# Controller_Board_Interface.net
KiCad netlist of a schematic drawn in Altium Designer
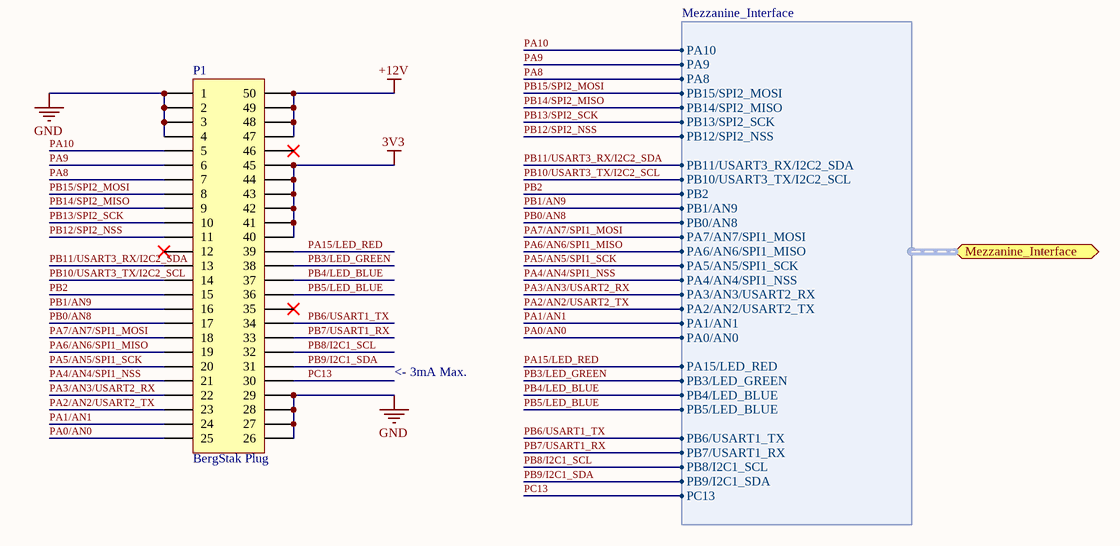
[diagram p0: Controller_Board_Interface.SchDoc]

(export (version "E")
  (design (tool "Eeschema 10.0.6"))
  (components
    (comp (ref "P1")
      (value "CONN 50POS Bergstak Plug 0.02\"")
      (footprint "CONN, Bergstak 50 Pos Plug")
      (description "50 Position Connector Plug, Outer Shroud Contacts Surface Mount Gold")
      (fields (field (name "SERIES") "BergStak Plug"))
      (libsource (lib "Schematic Diagrams") (part "CONN 50POS Bergstak Plug 0.02{dblquote}"))
    )
  )
  (nets
    (net (code "2") (name "+12V") (class "Default")
      (node (ref "P1") (pin "47") (pinfunction "47_47") (pintype "passive"))
      (node (ref "P1") (pin "48") (pinfunction "48_48") (pintype "passive"))
      (node (ref "P1") (pin "49") (pinfunction "49_49") (pintype "passive"))
      (node (ref "P1") (pin "50") (pinfunction "50_50") (pintype "passive"))
    )
    (net (code "3") (name "/PA0{slash}AN0") (class "Default")
      (node (ref "P1") (pin "25") (pinfunction "25_25") (pintype "passive"))
    )
    (net (code "4") (name "/PA1{slash}AN1") (class "Default")
      (node (ref "P1") (pin "24") (pinfunction "24_24") (pintype "passive"))
    )
    (net (code "5") (name "/PA2{slash}AN2{slash}USART2_TX") (class "Default")
      (node (ref "P1") (pin "23") (pinfunction "23_23") (pintype "passive"))
    )
    (net (code "6") (name "/PA3{slash}AN3{slash}USART2_RX") (class "Default")
      (node (ref "P1") (pin "22") (pinfunction "22_22") (pintype "passive"))
    )
    (net (code "7") (name "/PA4{slash}AN4{slash}SPI1_NSS") (class "Default")
      (node (ref "P1") (pin "21") (pinfunction "21_21") (pintype "passive"))
    )
    (net (code "8") (name "/PA5{slash}AN5{slash}SPI1_SCK") (class "Default")
      (node (ref "P1") (pin "20") (pinfunction "20_20") (pintype "passive"))
    )
    (net (code "9") (name "/PA6{slash}AN6{slash}SPI1_MISO") (class "Default")
      (node (ref "P1") (pin "19") (pinfunction "19_19") (pintype "passive"))
    )
    (net (code "10") (name "/PA7{slash}AN7{slash}SPI1_MOSI") (class "Default")
      (node (ref "P1") (pin "18") (pinfunction "18_18") (pintype "passive"))
    )
    (net (code "11") (name "/PA8") (class "Default")
      (node (ref "P1") (pin "7") (pinfunction "7_7") (pintype "passive"))
    )
    (net (code "12") (name "/PA9") (class "Default")
      (node (ref "P1") (pin "6") (pinfunction "6_6") (pintype "passive"))
    )
    (net (code "13") (name "/PA10") (class "Default")
      (node (ref "P1") (pin "5") (pinfunction "5_5") (pintype "passive"))
    )
    (net (code "14") (name "/PA15{slash}LED_RED") (class "Default")
      (node (ref "P1") (pin "39") (pinfunction "39_39") (pintype "passive"))
    )
    (net (code "15") (name "/PB0{slash}AN8") (class "Default")
      (node (ref "P1") (pin "17") (pinfunction "17_17") (pintype "passive"))
    )
    (net (code "16") (name "/PB1{slash}AN9") (class "Default")
      (node (ref "P1") (pin "16") (pinfunction "16_16") (pintype "passive"))
    )
    (net (code "17") (name "/PB2") (class "Default")
      (node (ref "P1") (pin "15") (pinfunction "15_15") (pintype "passive"))
    )
    (net (code "18") (name "/PB3{slash}LED_GREEN") (class "Default")
      (node (ref "P1") (pin "38") (pinfunction "38_38") (pintype "passive"))
    )
    (net (code "19") (name "/PB4{slash}LED_BLUE") (class "Default")
      (node (ref "P1") (pin "37") (pinfunction "37_37") (pintype "passive"))
    )
    (net (code "20") (name "/PB5{slash}LED_BLUE") (class "Default")
      (node (ref "P1") (pin "36") (pinfunction "36_36") (pintype "passive"))
    )
    (net (code "21") (name "/PB6{slash}USART1_TX") (class "Default")
      (node (ref "P1") (pin "34") (pinfunction "34_34") (pintype "passive"))
    )
    (net (code "22") (name "/PB7{slash}USART1_RX") (class "Default")
      (node (ref "P1") (pin "33") (pinfunction "33_33") (pintype "passive"))
    )
    (net (code "23") (name "/PB8{slash}I2C1_SCL") (class "Default")
      (node (ref "P1") (pin "32") (pinfunction "32_32") (pintype "passive"))
    )
    (net (code "24") (name "/PB9{slash}I2C1_SDA") (class "Default")
      (node (ref "P1") (pin "31") (pinfunction "31_31") (pintype "passive"))
    )
    (net (code "25") (name "/PB10{slash}USART3_TX{slash}I2C2_SCL") (class "Default")
      (node (ref "P1") (pin "14") (pinfunction "14_14") (pintype "passive"))
    )
    (net (code "26") (name "/PB11{slash}USART3_RX{slash}I2C2_SDA") (class "Default")
      (node (ref "P1") (pin "13") (pinfunction "13_13") (pintype "passive"))
    )
    (net (code "27") (name "/PB12{slash}SPI2_NSS") (class "Default")
      (node (ref "P1") (pin "11") (pinfunction "11_11") (pintype "passive"))
    )
    (net (code "28") (name "/PB13{slash}SPI2_SCK") (class "Default")
      (node (ref "P1") (pin "10") (pinfunction "10_10") (pintype "passive"))
    )
    (net (code "29") (name "/PB14{slash}SPI2_MISO") (class "Default")
      (node (ref "P1") (pin "9") (pinfunction "9_9") (pintype "passive"))
    )
    (net (code "30") (name "/PB15{slash}SPI2_MOSI") (class "Default")
      (node (ref "P1") (pin "8") (pinfunction "8_8") (pintype "passive"))
    )
    (net (code "31") (name "/PC13") (class "Default")
      (node (ref "P1") (pin "30") (pinfunction "30_30") (pintype "passive"))
    )
    (net (code "33") (name "3V3") (class "Default")
      (node (ref "P1") (pin "40") (pinfunction "40_40") (pintype "passive"))
      (node (ref "P1") (pin "41") (pinfunction "41_41") (pintype "passive"))
      (node (ref "P1") (pin "42") (pinfunction "42_42") (pintype "passive"))
      (node (ref "P1") (pin "43") (pinfunction "43_43") (pintype "passive"))
      (node (ref "P1") (pin "44") (pinfunction "44_44") (pintype "passive"))
      (node (ref "P1") (pin "45") (pinfunction "45_45") (pintype "passive"))
    )
    (net (code "34") (name "GND") (class "Default")
      (node (ref "P1") (pin "1") (pinfunction "1_1") (pintype "passive"))
      (node (ref "P1") (pin "2") (pinfunction "2_2") (pintype "passive"))
      (node (ref "P1") (pin "26") (pinfunction "26_26") (pintype "passive"))
      (node (ref "P1") (pin "27") (pinfunction "27_27") (pintype "passive"))
      (node (ref "P1") (pin "28") (pinfunction "28_28") (pintype "passive"))
      (node (ref "P1") (pin "29") (pinfunction "29_29") (pintype "passive"))
      (node (ref "P1") (pin "3") (pinfunction "3_3") (pintype "passive"))
      (node (ref "P1") (pin "4") (pinfunction "4_4") (pintype "passive"))
    )
    (net (code "35") (name "unconnected-(P1-Pad12)") (class "Default")
      (node (ref "P1") (pin "12") (pinfunction "12_12") (pintype "passive+no_connect"))
    )
    (net (code "36") (name "unconnected-(P1-Pad35)") (class "Default")
      (node (ref "P1") (pin "35") (pinfunction "35_35") (pintype "passive+no_connect"))
    )
    (net (code "37") (name "unconnected-(P1-Pad46)") (class "Default")
      (node (ref "P1") (pin "46") (pinfunction "46_46") (pintype "passive+no_connect"))
    )
  )
)
